# regsimple2addfp.net
KiCad netlist of a schematic drawn in EAGLE
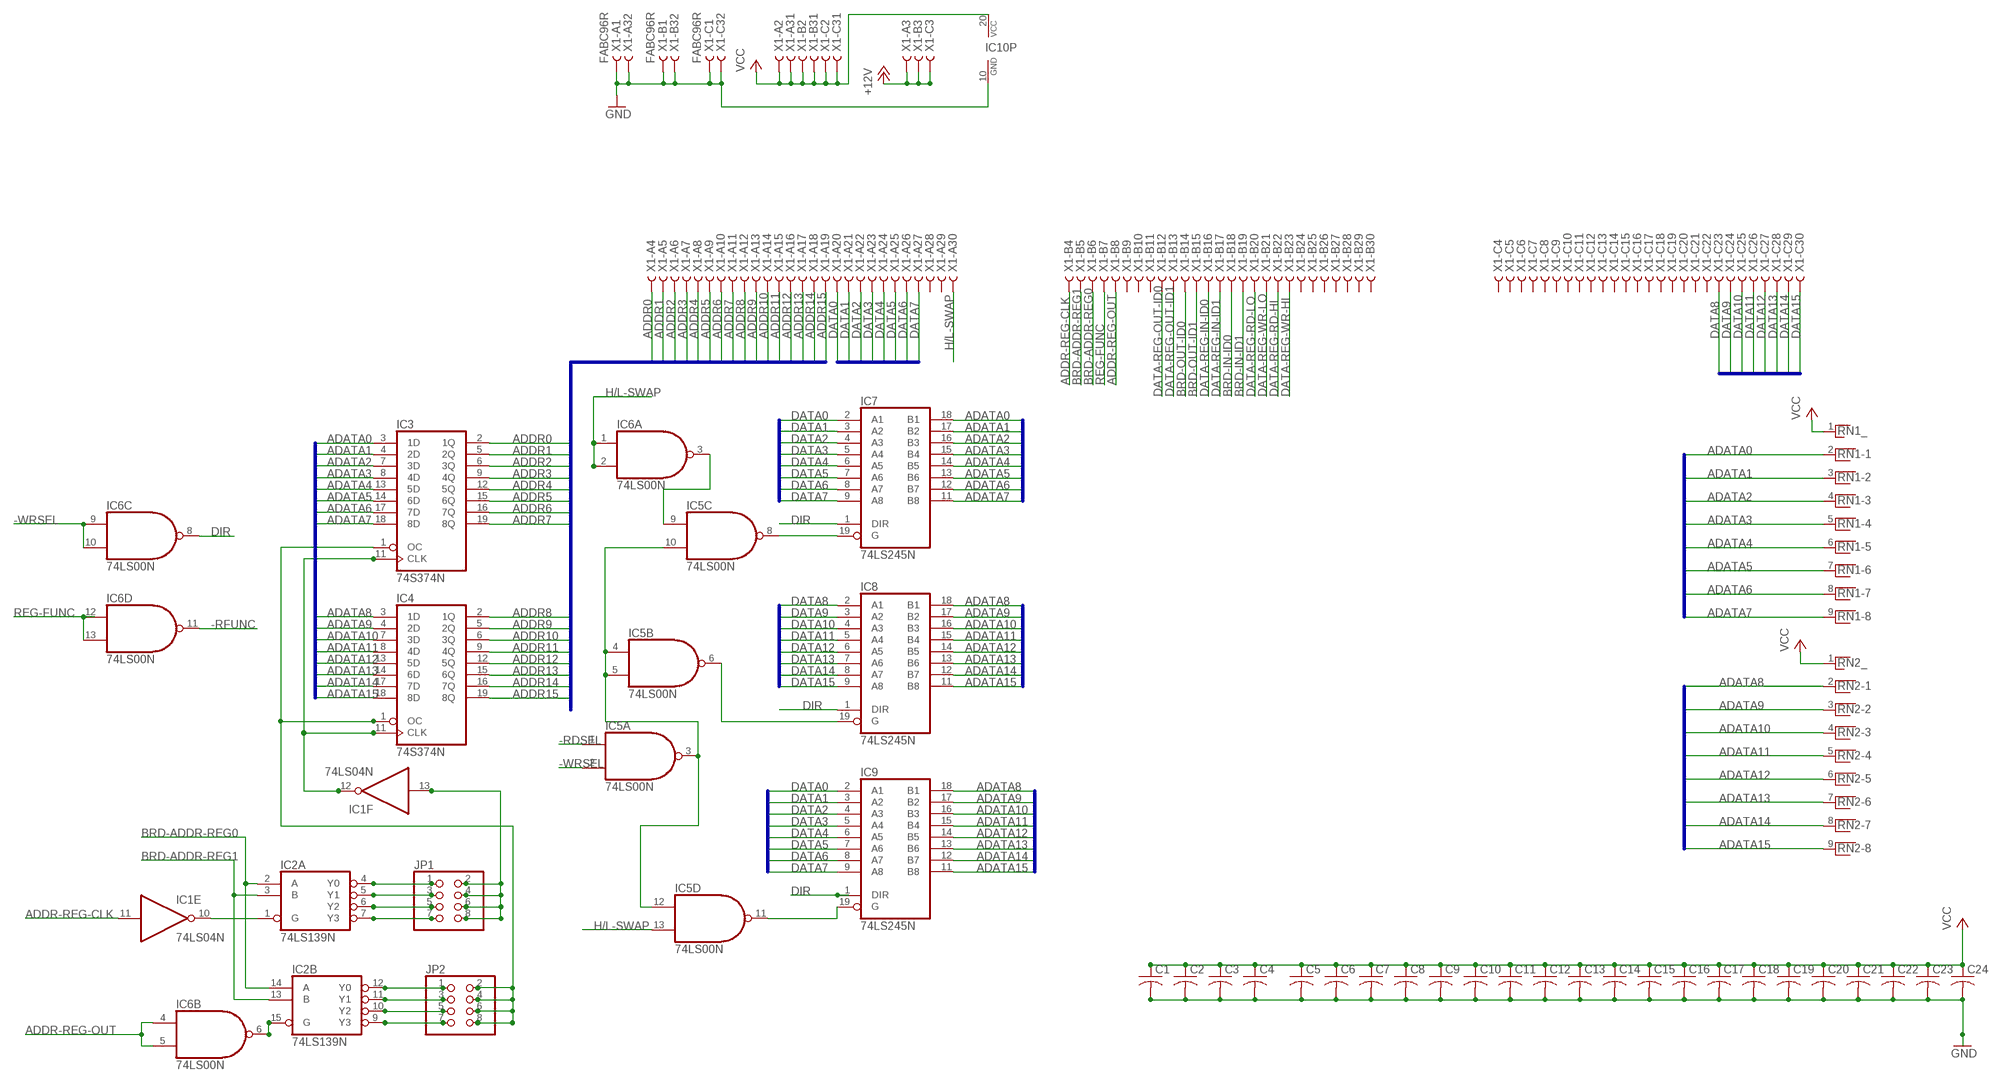
[diagram p0: schematic, sheet 1]
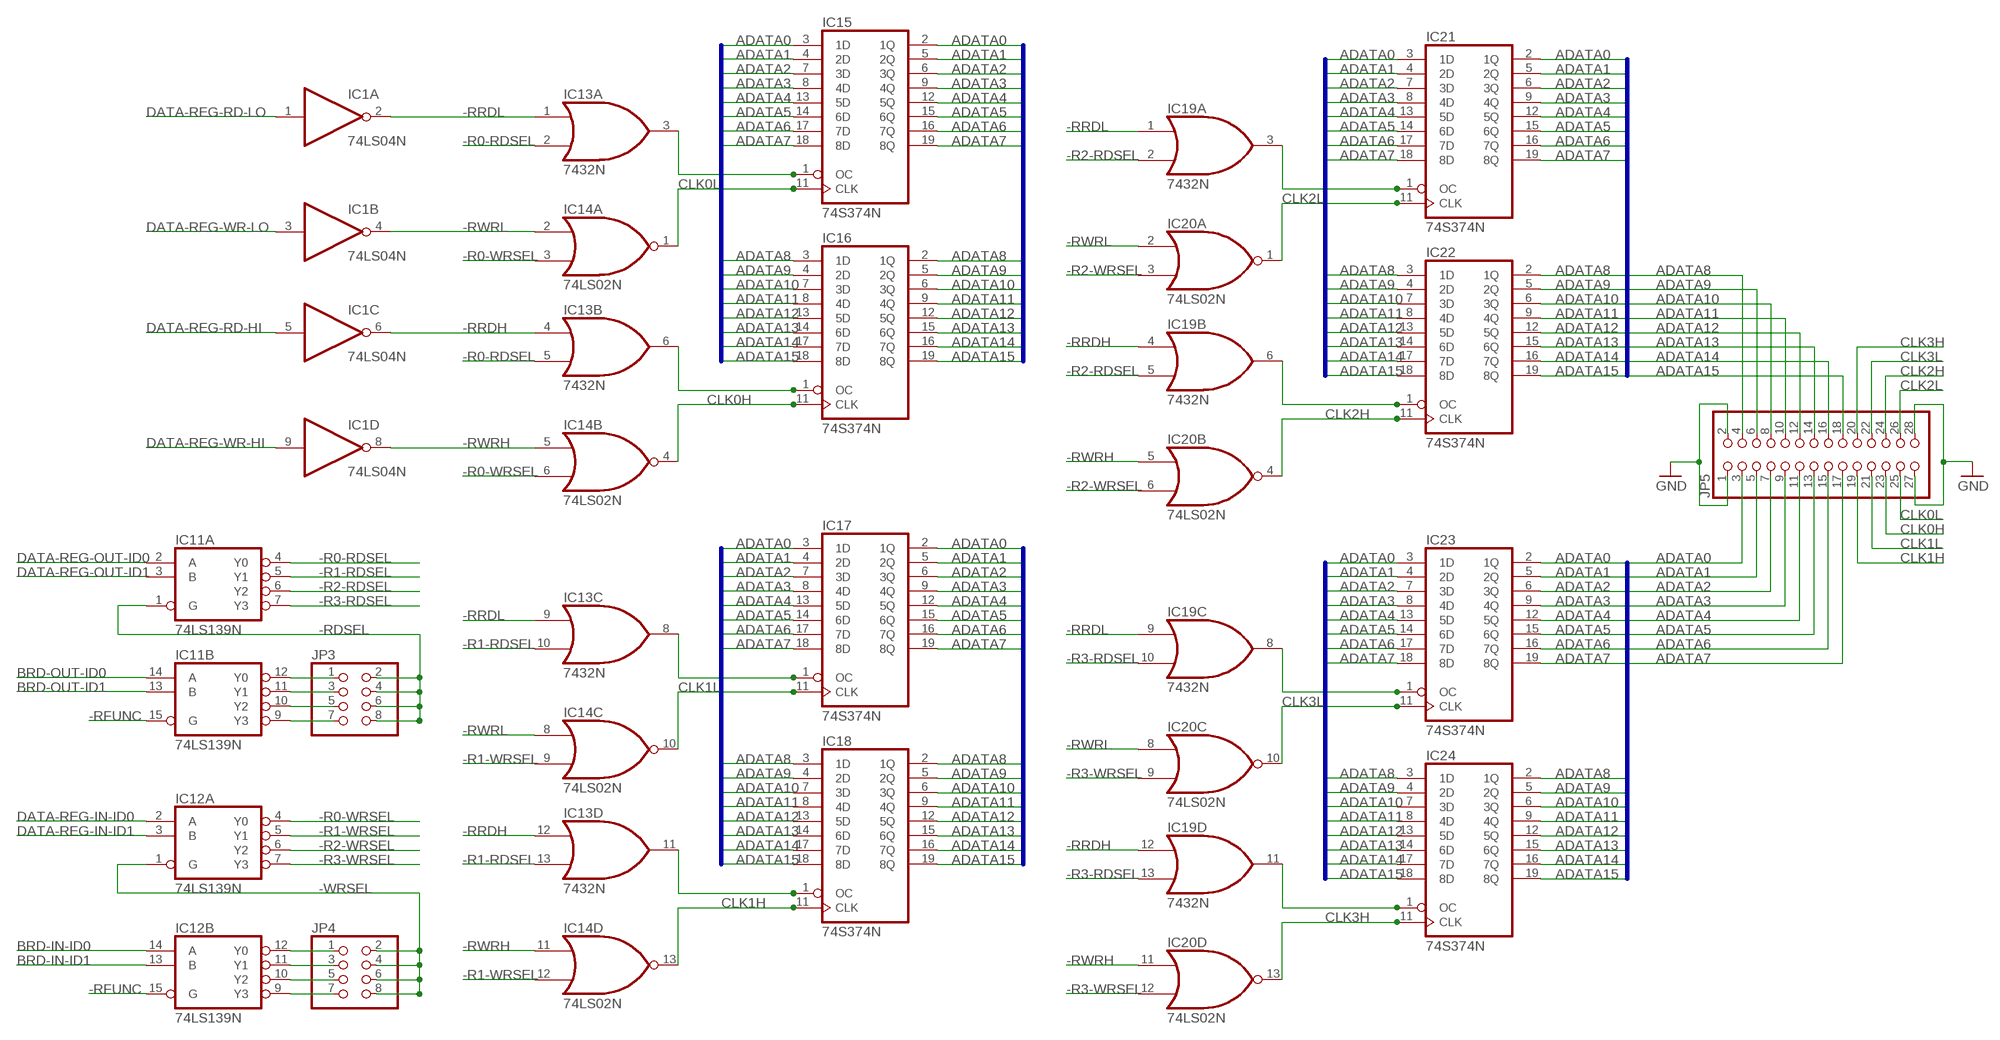
[diagram p1: schematic, sheet 2]

(export (version "E")
  (design (tool "Eeschema 10.0.6"))
  (components
    (comp (ref "IC1")
      (value "74LS04N")
      (footprint "eagle-import:DIL14")
      (libsource (lib "eagle-import") (part "7404NLS"))
    )
    (comp (ref "IC11")
      (value "74LS139N")
      (footprint "eagle-import:DIL16")
      (libsource (lib "eagle-import") (part "74139NLS"))
    )
    (comp (ref "IC12")
      (value "74LS139N")
      (footprint "eagle-import:DIL16")
      (libsource (lib "eagle-import") (part "74139NLS"))
    )
    (comp (ref "IC13")
      (value "7432N")
      (footprint "eagle-import:DIL14")
      (libsource (lib "eagle-import") (part "7432N"))
    )
    (comp (ref "IC14")
      (value "74LS02N")
      (footprint "eagle-import:DIL14")
      (libsource (lib "eagle-import") (part "7402NLS"))
    )
    (comp (ref "IC15")
      (value "74S374N")
      (footprint "eagle-import:DIL20")
      (libsource (lib "eagle-import") (part "74374NS"))
    )
    (comp (ref "IC16")
      (value "74S374N")
      (footprint "eagle-import:DIL20")
      (libsource (lib "eagle-import") (part "74374NS"))
    )
    (comp (ref "IC17")
      (value "74S374N")
      (footprint "eagle-import:DIL20")
      (libsource (lib "eagle-import") (part "74374NS"))
    )
    (comp (ref "IC18")
      (value "74S374N")
      (footprint "eagle-import:DIL20")
      (libsource (lib "eagle-import") (part "74374NS"))
    )
    (comp (ref "IC19")
      (value "7432N")
      (footprint "eagle-import:DIL14")
      (libsource (lib "eagle-import") (part "7432N"))
    )
    (comp (ref "IC20")
      (value "74LS02N")
      (footprint "eagle-import:DIL14")
      (libsource (lib "eagle-import") (part "7402NLS"))
    )
    (comp (ref "IC21")
      (value "74S374N")
      (footprint "eagle-import:DIL20")
      (libsource (lib "eagle-import") (part "74374NS"))
    )
    (comp (ref "IC22")
      (value "74S374N")
      (footprint "eagle-import:DIL20")
      (libsource (lib "eagle-import") (part "74374NS"))
    )
    (comp (ref "IC23")
      (value "74S374N")
      (footprint "eagle-import:DIL20")
      (libsource (lib "eagle-import") (part "74374NS"))
    )
    (comp (ref "IC24")
      (value "74S374N")
      (footprint "eagle-import:DIL20")
      (libsource (lib "eagle-import") (part "74374NS"))
    )
    (comp (ref "JP3")
      (value "PINHD-2X4")
      (footprint "eagle-import:2X04")
      (libsource (lib "eagle-import") (part "PINHD-2X4"))
    )
    (comp (ref "JP4")
      (value "PINHD-2X4")
      (footprint "eagle-import:2X04")
      (libsource (lib "eagle-import") (part "PINHD-2X4"))
    )
    (comp (ref "JP5")
      (value "PINHD-2X14")
      (footprint "eagle-import:2X14")
      (libsource (lib "eagle-import") (part "PINHD-2X14"))
    )
    (comp (ref "C1")
      (value "C-US025-040X050")
      (footprint "eagle-import:C025-040X050")
      (libsource (lib "eagle-import") (part "C-US025-040X050"))
    )
    (comp (ref "C2")
      (value "C-US025-040X050")
      (footprint "eagle-import:C025-040X050")
      (libsource (lib "eagle-import") (part "C-US025-040X050"))
    )
    (comp (ref "C3")
      (value "C-US025-040X050")
      (footprint "eagle-import:C025-040X050")
      (libsource (lib "eagle-import") (part "C-US025-040X050"))
    )
    (comp (ref "C4")
      (value "C-US025-040X050")
      (footprint "eagle-import:C025-040X050")
      (libsource (lib "eagle-import") (part "C-US025-040X050"))
    )
    (comp (ref "C5")
      (value "C-US025-040X050")
      (footprint "eagle-import:C025-040X050")
      (libsource (lib "eagle-import") (part "C-US025-040X050"))
    )
    (comp (ref "C6")
      (value "C-US025-040X050")
      (footprint "eagle-import:C025-040X050")
      (libsource (lib "eagle-import") (part "C-US025-040X050"))
    )
    (comp (ref "C7")
      (value "C-US025-040X050")
      (footprint "eagle-import:C025-040X050")
      (libsource (lib "eagle-import") (part "C-US025-040X050"))
    )
    (comp (ref "C8")
      (value "C-US025-040X050")
      (footprint "eagle-import:C025-040X050")
      (libsource (lib "eagle-import") (part "C-US025-040X050"))
    )
    (comp (ref "C9")
      (value "C-US025-040X050")
      (footprint "eagle-import:C025-040X050")
      (libsource (lib "eagle-import") (part "C-US025-040X050"))
    )
    (comp (ref "C10")
      (value "C-US025-040X050")
      (footprint "eagle-import:C025-040X050")
      (libsource (lib "eagle-import") (part "C-US025-040X050"))
    )
    (comp (ref "C11")
      (value "C-US025-040X050")
      (footprint "eagle-import:C025-040X050")
      (libsource (lib "eagle-import") (part "C-US025-040X050"))
    )
    (comp (ref "C12")
      (value "C-US025-040X050")
      (footprint "eagle-import:C025-040X050")
      (libsource (lib "eagle-import") (part "C-US025-040X050"))
    )
    (comp (ref "C13")
      (value "C-US025-040X050")
      (footprint "eagle-import:C025-040X050")
      (libsource (lib "eagle-import") (part "C-US025-040X050"))
    )
    (comp (ref "C14")
      (value "C-US025-040X050")
      (footprint "eagle-import:C025-040X050")
      (libsource (lib "eagle-import") (part "C-US025-040X050"))
    )
    (comp (ref "C15")
      (value "C-US025-040X050")
      (footprint "eagle-import:C025-040X050")
      (libsource (lib "eagle-import") (part "C-US025-040X050"))
    )
    (comp (ref "C16")
      (value "C-US025-040X050")
      (footprint "eagle-import:C025-040X050")
      (libsource (lib "eagle-import") (part "C-US025-040X050"))
    )
    (comp (ref "C17")
      (value "C-US025-040X050")
      (footprint "eagle-import:C025-040X050")
      (libsource (lib "eagle-import") (part "C-US025-040X050"))
    )
    (comp (ref "C18")
      (value "C-US025-040X050")
      (footprint "eagle-import:C025-040X050")
      (libsource (lib "eagle-import") (part "C-US025-040X050"))
    )
    (comp (ref "C19")
      (value "C-US025-040X050")
      (footprint "eagle-import:C025-040X050")
      (libsource (lib "eagle-import") (part "C-US025-040X050"))
    )
    (comp (ref "C20")
      (value "C-US025-040X050")
      (footprint "eagle-import:C025-040X050")
      (libsource (lib "eagle-import") (part "C-US025-040X050"))
    )
    (comp (ref "C21")
      (value "C-US025-040X050")
      (footprint "eagle-import:C025-040X050")
      (libsource (lib "eagle-import") (part "C-US025-040X050"))
    )
    (comp (ref "C22")
      (value "C-US025-040X050")
      (footprint "eagle-import:C025-040X050")
      (libsource (lib "eagle-import") (part "C-US025-040X050"))
    )
    (comp (ref "C23")
      (value "C-US025-040X050")
      (footprint "eagle-import:C025-040X050")
      (libsource (lib "eagle-import") (part "C-US025-040X050"))
    )
    (comp (ref "C24")
      (value "C-US025-040X050")
      (footprint "eagle-import:C025-040X050")
      (libsource (lib "eagle-import") (part "C-US025-040X050"))
    )
    (comp (ref "IC2")
      (value "74LS139N")
      (footprint "eagle-import:DIL16")
      (libsource (lib "eagle-import") (part "74139NLS"))
    )
    (comp (ref "IC3")
      (value "74S374N")
      (footprint "eagle-import:DIL20")
      (libsource (lib "eagle-import") (part "74374NS"))
    )
    (comp (ref "IC4")
      (value "74S374N")
      (footprint "eagle-import:DIL20")
      (libsource (lib "eagle-import") (part "74374NS"))
    )
    (comp (ref "IC5")
      (value "74LS00N")
      (footprint "eagle-import:DIL14")
      (libsource (lib "eagle-import") (part "7400NLS"))
    )
    (comp (ref "IC6")
      (value "74LS00N")
      (footprint "eagle-import:DIL14")
      (libsource (lib "eagle-import") (part "7400NLS"))
    )
    (comp (ref "IC7")
      (value "74LS245N")
      (footprint "eagle-import:DIL20")
      (libsource (lib "eagle-import") (part "74245NLS"))
    )
    (comp (ref "IC8")
      (value "74LS245N")
      (footprint "eagle-import:DIL20")
      (libsource (lib "eagle-import") (part "74245NLS"))
    )
    (comp (ref "IC9")
      (value "74LS245N")
      (footprint "eagle-import:DIL20")
      (libsource (lib "eagle-import") (part "74245NLS"))
    )
    (comp (ref "IC10")
      (value "74S244N")
      (footprint "eagle-import:DIL20")
      (libsource (lib "eagle-import") (part "74244NS"))
    )
    (comp (ref "JP1")
      (value "PINHD-2X4")
      (footprint "eagle-import:2X04")
      (libsource (lib "eagle-import") (part "PINHD-2X4"))
    )
    (comp (ref "JP2")
      (value "PINHD-2X4")
      (footprint "eagle-import:2X04")
      (libsource (lib "eagle-import") (part "PINHD-2X4"))
    )
    (comp (ref "RN1")
      (value "RNX8")
      (footprint "eagle-import:RN-9")
      (libsource (lib "eagle-import") (part "RNX8"))
    )
    (comp (ref "RN2")
      (value "RNX8")
      (footprint "eagle-import:RN-9")
      (libsource (lib "eagle-import") (part "RNX8"))
    )
    (comp (ref "X1")
      (value "FABC96R")
      (footprint "eagle-import:FABC96R")
      (libsource (lib "eagle-import") (part "FABC96R"))
    )
  )
  (nets
    (net (code "1") (name "+12V") (class "Default")
      (node (ref "X1") (pin "A3") (pinfunction "B_A3") (pintype "passive"))
      (node (ref "X1") (pin "B3") (pinfunction "B_B3") (pintype "passive"))
      (node (ref "X1") (pin "C3") (pinfunction "B_C3") (pintype "passive"))
    )
    (net (code "2") (name "-R0-RDSEL") (class "Default")
      (node (ref "IC11") (pin "4") (pinfunction "Y0_4") (pintype "output"))
      (node (ref "IC13") (pin "2") (pinfunction "I1_2") (pintype "input"))
      (node (ref "IC13") (pin "5") (pinfunction "I1_5") (pintype "input"))
    )
    (net (code "3") (name "-R0-WRSEL") (class "Default")
      (node (ref "IC12") (pin "4") (pinfunction "Y0_4") (pintype "output"))
      (node (ref "IC14") (pin "3") (pinfunction "I1_3") (pintype "input"))
      (node (ref "IC14") (pin "6") (pinfunction "I1_6") (pintype "input"))
    )
    (net (code "4") (name "-R1-RDSEL") (class "Default")
      (node (ref "IC11") (pin "5") (pinfunction "Y1_5") (pintype "output"))
      (node (ref "IC13") (pin "10") (pinfunction "I1_10") (pintype "input"))
      (node (ref "IC13") (pin "13") (pinfunction "I1_13") (pintype "input"))
    )
    (net (code "5") (name "-R1-WRSEL") (class "Default")
      (node (ref "IC12") (pin "5") (pinfunction "Y1_5") (pintype "output"))
      (node (ref "IC14") (pin "12") (pinfunction "I1_12") (pintype "input"))
      (node (ref "IC14") (pin "9") (pinfunction "I1_9") (pintype "input"))
    )
    (net (code "6") (name "-R2-RDSEL") (class "Default")
      (node (ref "IC11") (pin "6") (pinfunction "Y2_6") (pintype "output"))
      (node (ref "IC19") (pin "2") (pinfunction "I1_2") (pintype "input"))
      (node (ref "IC19") (pin "5") (pinfunction "I1_5") (pintype "input"))
    )
    (net (code "7") (name "-R2-WRSEL") (class "Default")
      (node (ref "IC12") (pin "6") (pinfunction "Y2_6") (pintype "output"))
      (node (ref "IC20") (pin "3") (pinfunction "I1_3") (pintype "input"))
      (node (ref "IC20") (pin "6") (pinfunction "I1_6") (pintype "input"))
    )
    (net (code "8") (name "-R3-RDSEL") (class "Default")
      (node (ref "IC11") (pin "7") (pinfunction "Y3_7") (pintype "output"))
      (node (ref "IC19") (pin "10") (pinfunction "I1_10") (pintype "input"))
      (node (ref "IC19") (pin "13") (pinfunction "I1_13") (pintype "input"))
    )
    (net (code "9") (name "-R3-WRSEL") (class "Default")
      (node (ref "IC12") (pin "7") (pinfunction "Y3_7") (pintype "output"))
      (node (ref "IC20") (pin "12") (pinfunction "I1_12") (pintype "input"))
      (node (ref "IC20") (pin "9") (pinfunction "I1_9") (pintype "input"))
    )
    (net (code "10") (name "-RDSEL") (class "Default")
      (node (ref "IC11") (pin "1") (pinfunction "G_1") (pintype "input"))
      (node (ref "IC5") (pin "1") (pinfunction "I0_1") (pintype "input"))
      (node (ref "JP3") (pin "2") (pinfunction "2_2") (pintype "passive"))
      (node (ref "JP3") (pin "4") (pinfunction "4_4") (pintype "passive"))
      (node (ref "JP3") (pin "6") (pinfunction "6_6") (pintype "passive"))
      (node (ref "JP3") (pin "8") (pinfunction "8_8") (pintype "passive"))
    )
    (net (code "11") (name "-RFUNC") (class "Default")
      (node (ref "IC11") (pin "15") (pinfunction "G_15") (pintype "input"))
      (node (ref "IC12") (pin "15") (pinfunction "G_15") (pintype "input"))
      (node (ref "IC6") (pin "11") (pinfunction "O_11") (pintype "output"))
    )
    (net (code "12") (name "-RRDH") (class "Default")
      (node (ref "IC1") (pin "6") (pinfunction "O_6") (pintype "output"))
      (node (ref "IC13") (pin "12") (pinfunction "I0_12") (pintype "input"))
      (node (ref "IC13") (pin "4") (pinfunction "I0_4") (pintype "input"))
      (node (ref "IC19") (pin "12") (pinfunction "I0_12") (pintype "input"))
      (node (ref "IC19") (pin "4") (pinfunction "I0_4") (pintype "input"))
    )
    (net (code "13") (name "-RRDL") (class "Default")
      (node (ref "IC1") (pin "2") (pinfunction "O_2") (pintype "output"))
      (node (ref "IC13") (pin "1") (pinfunction "I0_1") (pintype "input"))
      (node (ref "IC13") (pin "9") (pinfunction "I0_9") (pintype "input"))
      (node (ref "IC19") (pin "1") (pinfunction "I0_1") (pintype "input"))
      (node (ref "IC19") (pin "9") (pinfunction "I0_9") (pintype "input"))
    )
    (net (code "14") (name "-RWRH") (class "Default")
      (node (ref "IC1") (pin "8") (pinfunction "O_8") (pintype "output"))
      (node (ref "IC14") (pin "11") (pinfunction "I0_11") (pintype "input"))
      (node (ref "IC14") (pin "5") (pinfunction "I0_5") (pintype "input"))
      (node (ref "IC20") (pin "11") (pinfunction "I0_11") (pintype "input"))
      (node (ref "IC20") (pin "5") (pinfunction "I0_5") (pintype "input"))
    )
    (net (code "15") (name "-RWRL") (class "Default")
      (node (ref "IC1") (pin "4") (pinfunction "O_4") (pintype "output"))
      (node (ref "IC14") (pin "2") (pinfunction "I0_2") (pintype "input"))
      (node (ref "IC14") (pin "8") (pinfunction "I0_8") (pintype "input"))
      (node (ref "IC20") (pin "2") (pinfunction "I0_2") (pintype "input"))
      (node (ref "IC20") (pin "8") (pinfunction "I0_8") (pintype "input"))
    )
    (net (code "16") (name "-WRSEL") (class "Default")
      (node (ref "IC12") (pin "1") (pinfunction "G_1") (pintype "input"))
      (node (ref "IC5") (pin "2") (pinfunction "I1_2") (pintype "input"))
      (node (ref "IC6") (pin "10") (pinfunction "I1_10") (pintype "input"))
      (node (ref "IC6") (pin "9") (pinfunction "I0_9") (pintype "input"))
      (node (ref "JP4") (pin "2") (pinfunction "2_2") (pintype "passive"))
      (node (ref "JP4") (pin "4") (pinfunction "4_4") (pintype "passive"))
      (node (ref "JP4") (pin "6") (pinfunction "6_6") (pintype "passive"))
      (node (ref "JP4") (pin "8") (pinfunction "8_8") (pintype "passive"))
    )
    (net (code "17") (name "ADATA0") (class "Default")
      (node (ref "IC15") (pin "2") (pinfunction "1Q_2") (pintype "tri_state"))
      (node (ref "IC15") (pin "3") (pinfunction "1D_3") (pintype "input"))
      (node (ref "IC17") (pin "2") (pinfunction "1Q_2") (pintype "tri_state"))
      (node (ref "IC17") (pin "3") (pinfunction "1D_3") (pintype "input"))
      (node (ref "IC21") (pin "2") (pinfunction "1Q_2") (pintype "tri_state"))
      (node (ref "IC21") (pin "3") (pinfunction "1D_3") (pintype "input"))
      (node (ref "IC23") (pin "2") (pinfunction "1Q_2") (pintype "tri_state"))
      (node (ref "IC23") (pin "3") (pinfunction "1D_3") (pintype "input"))
      (node (ref "IC3") (pin "3") (pinfunction "1D_3") (pintype "input"))
      (node (ref "IC7") (pin "18") (pinfunction "B1_18") (pintype "bidirectional"))
      (node (ref "JP5") (pin "3") (pinfunction "3_3") (pintype "passive"))
      (node (ref "RN1") (pin "2") (pinfunction "1_2") (pintype "passive"))
    )
    (net (code "18") (name "ADATA1") (class "Default")
      (node (ref "IC15") (pin "4") (pinfunction "2D_4") (pintype "input"))
      (node (ref "IC15") (pin "5") (pinfunction "2Q_5") (pintype "tri_state"))
      (node (ref "IC17") (pin "4") (pinfunction "2D_4") (pintype "input"))
      (node (ref "IC17") (pin "5") (pinfunction "2Q_5") (pintype "tri_state"))
      (node (ref "IC21") (pin "4") (pinfunction "2D_4") (pintype "input"))
      (node (ref "IC21") (pin "5") (pinfunction "2Q_5") (pintype "tri_state"))
      (node (ref "IC23") (pin "4") (pinfunction "2D_4") (pintype "input"))
      (node (ref "IC23") (pin "5") (pinfunction "2Q_5") (pintype "tri_state"))
      (node (ref "IC3") (pin "4") (pinfunction "2D_4") (pintype "input"))
      (node (ref "IC7") (pin "17") (pinfunction "B2_17") (pintype "bidirectional"))
      (node (ref "JP5") (pin "5") (pinfunction "5_5") (pintype "passive"))
      (node (ref "RN1") (pin "3") (pinfunction "1_3") (pintype "passive"))
    )
    (net (code "19") (name "ADATA2") (class "Default")
      (node (ref "IC15") (pin "6") (pinfunction "3Q_6") (pintype "tri_state"))
      (node (ref "IC15") (pin "7") (pinfunction "3D_7") (pintype "input"))
      (node (ref "IC17") (pin "6") (pinfunction "3Q_6") (pintype "tri_state"))
      (node (ref "IC17") (pin "7") (pinfunction "3D_7") (pintype "input"))
      (node (ref "IC21") (pin "6") (pinfunction "3Q_6") (pintype "tri_state"))
      (node (ref "IC21") (pin "7") (pinfunction "3D_7") (pintype "input"))
      (node (ref "IC23") (pin "6") (pinfunction "3Q_6") (pintype "tri_state"))
      (node (ref "IC23") (pin "7") (pinfunction "3D_7") (pintype "input"))
      (node (ref "IC3") (pin "7") (pinfunction "3D_7") (pintype "input"))
      (node (ref "IC7") (pin "16") (pinfunction "B3_16") (pintype "bidirectional"))
      (node (ref "JP5") (pin "7") (pinfunction "7_7") (pintype "passive"))
      (node (ref "RN1") (pin "4") (pinfunction "1_4") (pintype "passive"))
    )
    (net (code "20") (name "ADATA3") (class "Default")
      (node (ref "IC15") (pin "8") (pinfunction "4D_8") (pintype "input"))
      (node (ref "IC15") (pin "9") (pinfunction "4Q_9") (pintype "tri_state"))
      (node (ref "IC17") (pin "8") (pinfunction "4D_8") (pintype "input"))
      (node (ref "IC17") (pin "9") (pinfunction "4Q_9") (pintype "tri_state"))
      (node (ref "IC21") (pin "8") (pinfunction "4D_8") (pintype "input"))
      (node (ref "IC21") (pin "9") (pinfunction "4Q_9") (pintype "tri_state"))
      (node (ref "IC23") (pin "8") (pinfunction "4D_8") (pintype "input"))
      (node (ref "IC23") (pin "9") (pinfunction "4Q_9") (pintype "tri_state"))
      (node (ref "IC3") (pin "8") (pinfunction "4D_8") (pintype "input"))
      (node (ref "IC7") (pin "15") (pinfunction "B4_15") (pintype "bidirectional"))
      (node (ref "JP5") (pin "9") (pinfunction "9_9") (pintype "passive"))
      (node (ref "RN1") (pin "5") (pinfunction "1_5") (pintype "passive"))
    )
    (net (code "21") (name "ADATA4") (class "Default")
      (node (ref "IC15") (pin "12") (pinfunction "5Q_12") (pintype "tri_state"))
      (node (ref "IC15") (pin "13") (pinfunction "5D_13") (pintype "input"))
      (node (ref "IC17") (pin "12") (pinfunction "5Q_12") (pintype "tri_state"))
      (node (ref "IC17") (pin "13") (pinfunction "5D_13") (pintype "input"))
      (node (ref "IC21") (pin "12") (pinfunction "5Q_12") (pintype "tri_state"))
      (node (ref "IC21") (pin "13") (pinfunction "5D_13") (pintype "input"))
      (node (ref "IC23") (pin "12") (pinfunction "5Q_12") (pintype "tri_state"))
      (node (ref "IC23") (pin "13") (pinfunction "5D_13") (pintype "input"))
      (node (ref "IC3") (pin "13") (pinfunction "5D_13") (pintype "input"))
      (node (ref "IC7") (pin "14") (pinfunction "B5_14") (pintype "bidirectional"))
      (node (ref "JP5") (pin "11") (pinfunction "11_11") (pintype "passive"))
      (node (ref "RN1") (pin "6") (pinfunction "1_6") (pintype "passive"))
    )
    (net (code "22") (name "ADATA5") (class "Default")
      (node (ref "IC15") (pin "14") (pinfunction "6D_14") (pintype "input"))
      (node (ref "IC15") (pin "15") (pinfunction "6Q_15") (pintype "tri_state"))
      (node (ref "IC17") (pin "14") (pinfunction "6D_14") (pintype "input"))
      (node (ref "IC17") (pin "15") (pinfunction "6Q_15") (pintype "tri_state"))
      (node (ref "IC21") (pin "14") (pinfunction "6D_14") (pintype "input"))
      (node (ref "IC21") (pin "15") (pinfunction "6Q_15") (pintype "tri_state"))
      (node (ref "IC23") (pin "14") (pinfunction "6D_14") (pintype "input"))
      (node (ref "IC23") (pin "15") (pinfunction "6Q_15") (pintype "tri_state"))
      (node (ref "IC3") (pin "14") (pinfunction "6D_14") (pintype "input"))
      (node (ref "IC7") (pin "13") (pinfunction "B6_13") (pintype "bidirectional"))
      (node (ref "JP5") (pin "13") (pinfunction "13_13") (pintype "passive"))
      (node (ref "RN1") (pin "7") (pinfunction "1_7") (pintype "passive"))
    )
    (net (code "23") (name "ADATA6") (class "Default")
      (node (ref "IC15") (pin "16") (pinfunction "7Q_16") (pintype "tri_state"))
      (node (ref "IC15") (pin "17") (pinfunction "7D_17") (pintype "input"))
      (node (ref "IC17") (pin "16") (pinfunction "7Q_16") (pintype "tri_state"))
      (node (ref "IC17") (pin "17") (pinfunction "7D_17") (pintype "input"))
      (node (ref "IC21") (pin "16") (pinfunction "7Q_16") (pintype "tri_state"))
      (node (ref "IC21") (pin "17") (pinfunction "7D_17") (pintype "input"))
      (node (ref "IC23") (pin "16") (pinfunction "7Q_16") (pintype "tri_state"))
      (node (ref "IC23") (pin "17") (pinfunction "7D_17") (pintype "input"))
      (node (ref "IC3") (pin "17") (pinfunction "7D_17") (pintype "input"))
      (node (ref "IC7") (pin "12") (pinfunction "B7_12") (pintype "bidirectional"))
      (node (ref "JP5") (pin "15") (pinfunction "15_15") (pintype "passive"))
      (node (ref "RN1") (pin "8") (pinfunction "1_8") (pintype "passive"))
    )
    (net (code "24") (name "ADATA7") (class "Default")
      (node (ref "IC15") (pin "18") (pinfunction "8D_18") (pintype "input"))
      (node (ref "IC15") (pin "19") (pinfunction "8Q_19") (pintype "tri_state"))
      (node (ref "IC17") (pin "18") (pinfunction "8D_18") (pintype "input"))
      (node (ref "IC17") (pin "19") (pinfunction "8Q_19") (pintype "tri_state"))
      (node (ref "IC21") (pin "18") (pinfunction "8D_18") (pintype "input"))
      (node (ref "IC21") (pin "19") (pinfunction "8Q_19") (pintype "tri_state"))
      (node (ref "IC23") (pin "18") (pinfunction "8D_18") (pintype "input"))
      (node (ref "IC23") (pin "19") (pinfunction "8Q_19") (pintype "tri_state"))
      (node (ref "IC3") (pin "18") (pinfunction "8D_18") (pintype "input"))
      (node (ref "IC7") (pin "11") (pinfunction "B8_11") (pintype "bidirectional"))
      (node (ref "JP5") (pin "17") (pinfunction "17_17") (pintype "passive"))
      (node (ref "RN1") (pin "9") (pinfunction "1_9") (pintype "passive"))
    )
    (net (code "25") (name "ADATA8") (class "Default")
      (node (ref "IC16") (pin "2") (pinfunction "1Q_2") (pintype "tri_state"))
      (node (ref "IC16") (pin "3") (pinfunction "1D_3") (pintype "input"))
      (node (ref "IC18") (pin "2") (pinfunction "1Q_2") (pintype "tri_state"))
      (node (ref "IC18") (pin "3") (pinfunction "1D_3") (pintype "input"))
      (node (ref "IC22") (pin "2") (pinfunction "1Q_2") (pintype "tri_state"))
      (node (ref "IC22") (pin "3") (pinfunction "1D_3") (pintype "input"))
      (node (ref "IC24") (pin "2") (pinfunction "1Q_2") (pintype "tri_state"))
      (node (ref "IC24") (pin "3") (pinfunction "1D_3") (pintype "input"))
      (node (ref "IC4") (pin "3") (pinfunction "1D_3") (pintype "input"))
      (node (ref "IC8") (pin "18") (pinfunction "B1_18") (pintype "bidirectional"))
      (node (ref "IC9") (pin "18") (pinfunction "B1_18") (pintype "bidirectional"))
      (node (ref "JP5") (pin "4") (pinfunction "4_4") (pintype "passive"))
      (node (ref "RN2") (pin "2") (pinfunction "1_2") (pintype "passive"))
    )
    (net (code "26") (name "ADATA9") (class "Default")
      (node (ref "IC16") (pin "4") (pinfunction "2D_4") (pintype "input"))
      (node (ref "IC16") (pin "5") (pinfunction "2Q_5") (pintype "tri_state"))
      (node (ref "IC18") (pin "4") (pinfunction "2D_4") (pintype "input"))
      (node (ref "IC18") (pin "5") (pinfunction "2Q_5") (pintype "tri_state"))
      (node (ref "IC22") (pin "4") (pinfunction "2D_4") (pintype "input"))
      (node (ref "IC22") (pin "5") (pinfunction "2Q_5") (pintype "tri_state"))
      (node (ref "IC24") (pin "4") (pinfunction "2D_4") (pintype "input"))
      (node (ref "IC24") (pin "5") (pinfunction "2Q_5") (pintype "tri_state"))
      (node (ref "IC4") (pin "4") (pinfunction "2D_4") (pintype "input"))
      (node (ref "IC8") (pin "17") (pinfunction "B2_17") (pintype "bidirectional"))
      (node (ref "IC9") (pin "17") (pinfunction "B2_17") (pintype "bidirectional"))
      (node (ref "JP5") (pin "6") (pinfunction "6_6") (pintype "passive"))
      (node (ref "RN2") (pin "3") (pinfunction "1_3") (pintype "passive"))
    )
    (net (code "27") (name "ADATA10") (class "Default")
      (node (ref "IC16") (pin "6") (pinfunction "3Q_6") (pintype "tri_state"))
      (node (ref "IC16") (pin "7") (pinfunction "3D_7") (pintype "input"))
      (node (ref "IC18") (pin "6") (pinfunction "3Q_6") (pintype "tri_state"))
      (node (ref "IC18") (pin "7") (pinfunction "3D_7") (pintype "input"))
      (node (ref "IC22") (pin "6") (pinfunction "3Q_6") (pintype "tri_state"))
      (node (ref "IC22") (pin "7") (pinfunction "3D_7") (pintype "input"))
      (node (ref "IC24") (pin "6") (pinfunction "3Q_6") (pintype "tri_state"))
      (node (ref "IC24") (pin "7") (pinfunction "3D_7") (pintype "input"))
      (node (ref "IC4") (pin "7") (pinfunction "3D_7") (pintype "input"))
      (node (ref "IC8") (pin "16") (pinfunction "B3_16") (pintype "bidirectional"))
      (node (ref "IC9") (pin "16") (pinfunction "B3_16") (pintype "bidirectional"))
      (node (ref "JP5") (pin "8") (pinfunction "8_8") (pintype "passive"))
      (node (ref "RN2") (pin "4") (pinfunction "1_4") (pintype "passive"))
    )
    (net (code "28") (name "ADATA11") (class "Default")
      (node (ref "IC16") (pin "8") (pinfunction "4D_8") (pintype "input"))
      (node (ref "IC16") (pin "9") (pinfunction "4Q_9") (pintype "tri_state"))
      (node (ref "IC18") (pin "8") (pinfunction "4D_8") (pintype "input"))
      (node (ref "IC18") (pin "9") (pinfunction "4Q_9") (pintype "tri_state"))
      (node (ref "IC22") (pin "8") (pinfunction "4D_8") (pintype "input"))
      (node (ref "IC22") (pin "9") (pinfunction "4Q_9") (pintype "tri_state"))
      (node (ref "IC24") (pin "8") (pinfunction "4D_8") (pintype "input"))
      (node (ref "IC24") (pin "9") (pinfunction "4Q_9") (pintype "tri_state"))
      (node (ref "IC4") (pin "8") (pinfunction "4D_8") (pintype "input"))
      (node (ref "IC8") (pin "15") (pinfunction "B4_15") (pintype "bidirectional"))
      (node (ref "IC9") (pin "15") (pinfunction "B4_15") (pintype "bidirectional"))
      (node (ref "JP5") (pin "10") (pinfunction "10_10") (pintype "passive"))
      (node (ref "RN2") (pin "5") (pinfunction "1_5") (pintype "passive"))
    )
    (net (code "29") (name "ADATA12") (class "Default")
      (node (ref "IC16") (pin "12") (pinfunction "5Q_12") (pintype "tri_state"))
      (node (ref "IC16") (pin "13") (pinfunction "5D_13") (pintype "input"))
      (node (ref "IC18") (pin "12") (pinfunction "5Q_12") (pintype "tri_state"))
      (node (ref "IC18") (pin "13") (pinfunction "5D_13") (pintype "input"))
      (node (ref "IC22") (pin "12") (pinfunction "5Q_12") (pintype "tri_state"))
      (node (ref "IC22") (pin "13") (pinfunction "5D_13") (pintype "input"))
      (node (ref "IC24") (pin "12") (pinfunction "5Q_12") (pintype "tri_state"))
      (node (ref "IC24") (pin "13") (pinfunction "5D_13") (pintype "input"))
      (node (ref "IC4") (pin "13") (pinfunction "5D_13") (pintype "input"))
      (node (ref "IC8") (pin "14") (pinfunction "B5_14") (pintype "bidirectional"))
      (node (ref "IC9") (pin "14") (pinfunction "B5_14") (pintype "bidirectional"))
      (node (ref "JP5") (pin "12") (pinfunction "12_12") (pintype "passive"))
      (node (ref "RN2") (pin "6") (pinfunction "1_6") (pintype "passive"))
    )
    (net (code "30") (name "ADATA13") (class "Default")
      (node (ref "IC16") (pin "14") (pinfunction "6D_14") (pintype "input"))
      (node (ref "IC16") (pin "15") (pinfunction "6Q_15") (pintype "tri_state"))
      (node (ref "IC18") (pin "14") (pinfunction "6D_14") (pintype "input"))
      (node (ref "IC18") (pin "15") (pinfunction "6Q_15") (pintype "tri_state"))
      (node (ref "IC22") (pin "14") (pinfunction "6D_14") (pintype "input"))
      (node (ref "IC22") (pin "15") (pinfunction "6Q_15") (pintype "tri_state"))
      (node (ref "IC24") (pin "14") (pinfunction "6D_14") (pintype "input"))
      (node (ref "IC24") (pin "15") (pinfunction "6Q_15") (pintype "tri_state"))
      (node (ref "IC4") (pin "14") (pinfunction "6D_14") (pintype "input"))
      (node (ref "IC8") (pin "13") (pinfunction "B6_13") (pintype "bidirectional"))
      (node (ref "IC9") (pin "13") (pinfunction "B6_13") (pintype "bidirectional"))
      (node (ref "JP5") (pin "14") (pinfunction "14_14") (pintype "passive"))
      (node (ref "RN2") (pin "7") (pinfunction "1_7") (pintype "passive"))
    )
    (net (code "31") (name "ADATA14") (class "Default")
      (node (ref "IC16") (pin "16") (pinfunction "7Q_16") (pintype "tri_state"))
      (node (ref "IC16") (pin "17") (pinfunction "7D_17") (pintype "input"))
      (node (ref "IC18") (pin "16") (pinfunction "7Q_16") (pintype "tri_state"))
      (node (ref "IC18") (pin "17") (pinfunction "7D_17") (pintype "input"))
      (node (ref "IC22") (pin "16") (pinfunction "7Q_16") (pintype "tri_state"))
      (node (ref "IC22") (pin "17") (pinfunction "7D_17") (pintype "input"))
      (node (ref "IC24") (pin "16") (pinfunction "7Q_16") (pintype "tri_state"))
      (node (ref "IC24") (pin "17") (pinfunction "7D_17") (pintype "input"))
      (node (ref "IC4") (pin "17") (pinfunction "7D_17") (pintype "input"))
      (node (ref "IC8") (pin "12") (pinfunction "B7_12") (pintype "bidirectional"))
      (node (ref "IC9") (pin "12") (pinfunction "B7_12") (pintype "bidirectional"))
      (node (ref "JP5") (pin "16") (pinfunction "16_16") (pintype "passive"))
      (node (ref "RN2") (pin "8") (pinfunction "1_8") (pintype "passive"))
    )
    (net (code "32") (name "ADATA15") (class "Default")
      (node (ref "IC16") (pin "18") (pinfunction "8D_18") (pintype "input"))
      (node (ref "IC16") (pin "19") (pinfunction "8Q_19") (pintype "tri_state"))
      (node (ref "IC18") (pin "18") (pinfunction "8D_18") (pintype "input"))
      (node (ref "IC18") (pin "19") (pinfunction "8Q_19") (pintype "tri_state"))
      (node (ref "IC22") (pin "18") (pinfunction "8D_18") (pintype "input"))
      (node (ref "IC22") (pin "19") (pinfunction "8Q_19") (pintype "tri_state"))
      (node (ref "IC24") (pin "18") (pinfunction "8D_18") (pintype "input"))
      (node (ref "IC24") (pin "19") (pinfunction "8Q_19") (pintype "tri_state"))
      (node (ref "IC4") (pin "18") (pinfunction "8D_18") (pintype "input"))
      (node (ref "IC8") (pin "11") (pinfunction "B8_11") (pintype "bidirectional"))
      (node (ref "IC9") (pin "11") (pinfunction "B8_11") (pintype "bidirectional"))
      (node (ref "JP5") (pin "18") (pinfunction "18_18") (pintype "passive"))
      (node (ref "RN2") (pin "9") (pinfunction "1_9") (pintype "passive"))
    )
    (net (code "33") (name "ADDR-REG-CLK") (class "Default")
      (node (ref "IC1") (pin "11") (pinfunction "I_11") (pintype "input"))
      (node (ref "X1") (pin "B4") (pinfunction "B_B4") (pintype "passive"))
    )
    (net (code "34") (name "ADDR-REG-OUT") (class "Default")
      (node (ref "IC6") (pin "4") (pinfunction "I0_4") (pintype "input"))
      (node (ref "IC6") (pin "5") (pinfunction "I1_5") (pintype "input"))
      (node (ref "X1") (pin "B8") (pinfunction "B_B8") (pintype "passive"))
    )
    (net (code "35") (name "ADDR0") (class "Default")
      (node (ref "IC3") (pin "2") (pinfunction "1Q_2") (pintype "tri_state"))
      (node (ref "X1") (pin "A4") (pinfunction "B_A4") (pintype "passive"))
    )
    (net (code "36") (name "ADDR1") (class "Default")
      (node (ref "IC3") (pin "5") (pinfunction "2Q_5") (pintype "tri_state"))
      (node (ref "X1") (pin "A5") (pinfunction "B_A5") (pintype "passive"))
    )
    (net (code "37") (name "ADDR2") (class "Default")
      (node (ref "IC3") (pin "6") (pinfunction "3Q_6") (pintype "tri_state"))
      (node (ref "X1") (pin "A6") (pinfunction "B_A6") (pintype "passive"))
    )
    (net (code "38") (name "ADDR3") (class "Default")
      (node (ref "IC3") (pin "9") (pinfunction "4Q_9") (pintype "tri_state"))
      (node (ref "X1") (pin "A7") (pinfunction "B_A7") (pintype "passive"))
    )
    (net (code "39") (name "ADDR4") (class "Default")
      (node (ref "IC3") (pin "12") (pinfunction "5Q_12") (pintype "tri_state"))
      (node (ref "X1") (pin "A8") (pinfunction "B_A8") (pintype "passive"))
    )
    (net (code "40") (name "ADDR5") (class "Default")
      (node (ref "IC3") (pin "15") (pinfunction "6Q_15") (pintype "tri_state"))
      (node (ref "X1") (pin "A9") (pinfunction "B_A9") (pintype "passive"))
    )
    (net (code "41") (name "ADDR6") (class "Default")
      (node (ref "IC3") (pin "16") (pinfunction "7Q_16") (pintype "tri_state"))
      (node (ref "X1") (pin "A10") (pinfunction "B_A10") (pintype "passive"))
    )
    (net (code "42") (name "ADDR7") (class "Default")
      (node (ref "IC3") (pin "19") (pinfunction "8Q_19") (pintype "tri_state"))
      (node (ref "X1") (pin "A11") (pinfunction "B_A11") (pintype "passive"))
    )
    (net (code "43") (name "ADDR8") (class "Default")
      (node (ref "IC4") (pin "2") (pinfunction "1Q_2") (pintype "tri_state"))
      (node (ref "X1") (pin "A12") (pinfunction "B_A12") (pintype "passive"))
    )
    (net (code "44") (name "ADDR9") (class "Default")
      (node (ref "IC4") (pin "5") (pinfunction "2Q_5") (pintype "tri_state"))
      (node (ref "X1") (pin "A13") (pinfunction "B_A13") (pintype "passive"))
    )
    (net (code "45") (name "ADDR10") (class "Default")
      (node (ref "IC4") (pin "6") (pinfunction "3Q_6") (pintype "tri_state"))
      (node (ref "X1") (pin "A14") (pinfunction "B_A14") (pintype "passive"))
    )
    (net (code "46") (name "ADDR11") (class "Default")
      (node (ref "IC4") (pin "9") (pinfunction "4Q_9") (pintype "tri_state"))
      (node (ref "X1") (pin "A15") (pinfunction "B_A15") (pintype "passive"))
    )
    (net (code "47") (name "ADDR12") (class "Default")
      (node (ref "IC4") (pin "12") (pinfunction "5Q_12") (pintype "tri_state"))
      (node (ref "X1") (pin "A16") (pinfunction "B_A16") (pintype "passive"))
    )
    (net (code "48") (name "ADDR13") (class "Default")
      (node (ref "IC4") (pin "15") (pinfunction "6Q_15") (pintype "tri_state"))
      (node (ref "X1") (pin "A17") (pinfunction "B_A17") (pintype "passive"))
    )
    (net (code "49") (name "ADDR14") (class "Default")
      (node (ref "IC4") (pin "16") (pinfunction "7Q_16") (pintype "tri_state"))
      (node (ref "X1") (pin "A18") (pinfunction "B_A18") (pintype "passive"))
    )
    (net (code "50") (name "ADDR15") (class "Default")
      (node (ref "IC4") (pin "19") (pinfunction "8Q_19") (pintype "tri_state"))
      (node (ref "X1") (pin "A19") (pinfunction "B_A19") (pintype "passive"))
    )
    (net (code "51") (name "BRD-ADDR-REG0") (class "Default")
      (node (ref "IC2") (pin "14") (pinfunction "A_14") (pintype "input"))
      (node (ref "IC2") (pin "2") (pinfunction "A_2") (pintype "input"))
      (node (ref "X1") (pin "B6") (pinfunction "B_B6") (pintype "passive"))
    )
    (net (code "52") (name "BRD-ADDR-REG1") (class "Default")
      (node (ref "IC2") (pin "13") (pinfunction "B_13") (pintype "input"))
      (node (ref "IC2") (pin "3") (pinfunction "B_3") (pintype "input"))
      (node (ref "X1") (pin "B5") (pinfunction "B_B5") (pintype "passive"))
    )
    (net (code "53") (name "BRD-IN-ID0") (class "Default")
      (node (ref "IC12") (pin "14") (pinfunction "A_14") (pintype "input"))
      (node (ref "X1") (pin "B18") (pinfunction "B_B18") (pintype "passive"))
    )
    (net (code "54") (name "BRD-IN-ID1") (class "Default")
      (node (ref "IC12") (pin "13") (pinfunction "B_13") (pintype "input"))
      (node (ref "X1") (pin "B19") (pinfunction "B_B19") (pintype "passive"))
    )
    (net (code "55") (name "BRD-OUT-ID0") (class "Default")
      (node (ref "IC11") (pin "14") (pinfunction "A_14") (pintype "input"))
      (node (ref "X1") (pin "B14") (pinfunction "B_B14") (pintype "passive"))
    )
    (net (code "56") (name "BRD-OUT-ID1") (class "Default")
      (node (ref "IC11") (pin "13") (pinfunction "B_13") (pintype "input"))
      (node (ref "X1") (pin "B15") (pinfunction "B_B15") (pintype "passive"))
    )
    (net (code "57") (name "CLK0H") (class "Default")
      (node (ref "IC14") (pin "4") (pinfunction "O_4") (pintype "output"))
      (node (ref "IC16") (pin "11") (pinfunction "CLK_11") (pintype "input"))
      (node (ref "JP5") (pin "23") (pinfunction "23_23") (pintype "passive"))
    )
    (net (code "58") (name "CLK0L") (class "Default")
      (node (ref "IC14") (pin "1") (pinfunction "O_1") (pintype "output"))
      (node (ref "IC15") (pin "11") (pinfunction "CLK_11") (pintype "input"))
      (node (ref "JP5") (pin "25") (pinfunction "25_25") (pintype "passive"))
    )
    (net (code "59") (name "CLK1H") (class "Default")
      (node (ref "IC14") (pin "13") (pinfunction "O_13") (pintype "output"))
      (node (ref "IC18") (pin "11") (pinfunction "CLK_11") (pintype "input"))
      (node (ref "JP5") (pin "19") (pinfunction "19_19") (pintype "passive"))
    )
    (net (code "60") (name "CLK1L") (class "Default")
      (node (ref "IC14") (pin "10") (pinfunction "O_10") (pintype "output"))
      (node (ref "IC17") (pin "11") (pinfunction "CLK_11") (pintype "input"))
      (node (ref "JP5") (pin "21") (pinfunction "21_21") (pintype "passive"))
    )
    (net (code "61") (name "CLK2H") (class "Default")
      (node (ref "IC20") (pin "4") (pinfunction "O_4") (pintype "output"))
      (node (ref "IC22") (pin "11") (pinfunction "CLK_11") (pintype "input"))
      (node (ref "JP5") (pin "24") (pinfunction "24_24") (pintype "passive"))
    )
    (net (code "62") (name "CLK2L") (class "Default")
      (node (ref "IC20") (pin "1") (pinfunction "O_1") (pintype "output"))
      (node (ref "IC21") (pin "11") (pinfunction "CLK_11") (pintype "input"))
      (node (ref "JP5") (pin "26") (pinfunction "26_26") (pintype "passive"))
    )
    (net (code "63") (name "CLK3H") (class "Default")
      (node (ref "IC20") (pin "13") (pinfunction "O_13") (pintype "output"))
      (node (ref "IC24") (pin "11") (pinfunction "CLK_11") (pintype "input"))
      (node (ref "JP5") (pin "20") (pinfunction "20_20") (pintype "passive"))
    )
    (net (code "64") (name "CLK3L") (class "Default")
      (node (ref "IC20") (pin "10") (pinfunction "O_10") (pintype "output"))
      (node (ref "IC23") (pin "11") (pinfunction "CLK_11") (pintype "input"))
      (node (ref "JP5") (pin "22") (pinfunction "22_22") (pintype "passive"))
    )
    (net (code "65") (name "DATA-REG-IN-ID0") (class "Default")
      (node (ref "IC12") (pin "2") (pinfunction "A_2") (pintype "input"))
      (node (ref "X1") (pin "B16") (pinfunction "B_B16") (pintype "passive"))
    )
    (net (code "66") (name "DATA-REG-IN-ID1") (class "Default")
      (node (ref "IC12") (pin "3") (pinfunction "B_3") (pintype "input"))
      (node (ref "X1") (pin "B17") (pinfunction "B_B17") (pintype "passive"))
    )
    (net (code "67") (name "DATA-REG-OUT-ID0") (class "Default")
      (node (ref "IC11") (pin "2") (pinfunction "A_2") (pintype "input"))
      (node (ref "X1") (pin "B12") (pinfunction "B_B12") (pintype "passive"))
    )
    (net (code "68") (name "DATA-REG-OUT-ID1") (class "Default")
      (node (ref "IC11") (pin "3") (pinfunction "B_3") (pintype "input"))
      (node (ref "X1") (pin "B13") (pinfunction "B_B13") (pintype "passive"))
    )
    (net (code "69") (name "DATA-REG-RD-HI") (class "Default")
      (node (ref "IC1") (pin "5") (pinfunction "I_5") (pintype "input"))
      (node (ref "X1") (pin "B22") (pinfunction "B_B22") (pintype "passive"))
    )
    (net (code "70") (name "DATA-REG-RD-LO") (class "Default")
      (node (ref "IC1") (pin "1") (pinfunction "I_1") (pintype "input"))
      (node (ref "X1") (pin "B20") (pinfunction "B_B20") (pintype "passive"))
    )
    (net (code "71") (name "DATA-REG-WR-HI") (class "Default")
      (node (ref "IC1") (pin "9") (pinfunction "I_9") (pintype "input"))
      (node (ref "X1") (pin "B23") (pinfunction "B_B23") (pintype "passive"))
    )
    (net (code "72") (name "DATA-REG-WR-LO") (class "Default")
      (node (ref "IC1") (pin "3") (pinfunction "I_3") (pintype "input"))
      (node (ref "X1") (pin "B21") (pinfunction "B_B21") (pintype "passive"))
    )
    (net (code "73") (name "DATA0") (class "Default")
      (node (ref "IC7") (pin "2") (pinfunction "A1_2") (pintype "bidirectional"))
      (node (ref "IC9") (pin "2") (pinfunction "A1_2") (pintype "bidirectional"))
      (node (ref "X1") (pin "A20") (pinfunction "B_A20") (pintype "passive"))
    )
    (net (code "74") (name "DATA1") (class "Default")
      (node (ref "IC7") (pin "3") (pinfunction "A2_3") (pintype "bidirectional"))
      (node (ref "IC9") (pin "3") (pinfunction "A2_3") (pintype "bidirectional"))
      (node (ref "X1") (pin "A21") (pinfunction "B_A21") (pintype "passive"))
    )
    (net (code "75") (name "DATA2") (class "Default")
      (node (ref "IC7") (pin "4") (pinfunction "A3_4") (pintype "bidirectional"))
      (node (ref "IC9") (pin "4") (pinfunction "A3_4") (pintype "bidirectional"))
      (node (ref "X1") (pin "A22") (pinfunction "B_A22") (pintype "passive"))
    )
    (net (code "76") (name "DATA3") (class "Default")
      (node (ref "IC7") (pin "5") (pinfunction "A4_5") (pintype "bidirectional"))
      (node (ref "IC9") (pin "5") (pinfunction "A4_5") (pintype "bidirectional"))
      (node (ref "X1") (pin "A23") (pinfunction "B_A23") (pintype "passive"))
    )
    (net (code "77") (name "DATA4") (class "Default")
      (node (ref "IC7") (pin "6") (pinfunction "A5_6") (pintype "bidirectional"))
      (node (ref "IC9") (pin "6") (pinfunction "A5_6") (pintype "bidirectional"))
      (node (ref "X1") (pin "A24") (pinfunction "B_A24") (pintype "passive"))
    )
    (net (code "78") (name "DATA5") (class "Default")
      (node (ref "IC7") (pin "7") (pinfunction "A6_7") (pintype "bidirectional"))
      (node (ref "IC9") (pin "7") (pinfunction "A6_7") (pintype "bidirectional"))
      (node (ref "X1") (pin "A25") (pinfunction "B_A25") (pintype "passive"))
    )
    (net (code "79") (name "DATA6") (class "Default")
      (node (ref "IC7") (pin "8") (pinfunction "A7_8") (pintype "bidirectional"))
      (node (ref "IC9") (pin "8") (pinfunction "A7_8") (pintype "bidirectional"))
      (node (ref "X1") (pin "A26") (pinfunction "B_A26") (pintype "passive"))
    )
    (net (code "80") (name "DATA7") (class "Default")
      (node (ref "IC7") (pin "9") (pinfunction "A8_9") (pintype "bidirectional"))
      (node (ref "IC9") (pin "9") (pinfunction "A8_9") (pintype "bidirectional"))
      (node (ref "X1") (pin "A27") (pinfunction "B_A27") (pintype "passive"))
    )
    (net (code "81") (name "DATA8") (class "Default")
      (node (ref "IC8") (pin "2") (pinfunction "A1_2") (pintype "bidirectional"))
      (node (ref "X1") (pin "C23") (pinfunction "B_C23") (pintype "passive"))
    )
    (net (code "82") (name "DATA9") (class "Default")
      (node (ref "IC8") (pin "3") (pinfunction "A2_3") (pintype "bidirectional"))
      (node (ref "X1") (pin "C24") (pinfunction "B_C24") (pintype "passive"))
    )
    (net (code "83") (name "DATA10") (class "Default")
      (node (ref "IC8") (pin "4") (pinfunction "A3_4") (pintype "bidirectional"))
      (node (ref "X1") (pin "C25") (pinfunction "B_C25") (pintype "passive"))
    )
    (net (code "84") (name "DATA11") (class "Default")
      (node (ref "IC8") (pin "5") (pinfunction "A4_5") (pintype "bidirectional"))
      (node (ref "X1") (pin "C26") (pinfunction "B_C26") (pintype "passive"))
    )
    (net (code "85") (name "DATA12") (class "Default")
      (node (ref "IC8") (pin "6") (pinfunction "A5_6") (pintype "bidirectional"))
      (node (ref "X1") (pin "C27") (pinfunction "B_C27") (pintype "passive"))
    )
    (net (code "86") (name "DATA13") (class "Default")
      (node (ref "IC8") (pin "7") (pinfunction "A6_7") (pintype "bidirectional"))
      (node (ref "X1") (pin "C28") (pinfunction "B_C28") (pintype "passive"))
    )
    (net (code "87") (name "DATA14") (class "Default")
      (node (ref "IC8") (pin "8") (pinfunction "A7_8") (pintype "bidirectional"))
      (node (ref "X1") (pin "C29") (pinfunction "B_C29") (pintype "passive"))
    )
    (net (code "88") (name "DATA15") (class "Default")
      (node (ref "IC8") (pin "9") (pinfunction "A8_9") (pintype "bidirectional"))
      (node (ref "X1") (pin "C30") (pinfunction "B_C30") (pintype "passive"))
    )
    (net (code "89") (name "DIR") (class "Default")
      (node (ref "IC6") (pin "8") (pinfunction "O_8") (pintype "output"))
      (node (ref "IC7") (pin "1") (pinfunction "DIR_1") (pintype "input"))
      (node (ref "IC8") (pin "1") (pinfunction "DIR_1") (pintype "input"))
      (node (ref "IC9") (pin "1") (pinfunction "DIR_1") (pintype "input"))
    )
    (net (code "90") (name "GND") (class "Default")
      (node (ref "C1") (pin "2") (pinfunction "2_2") (pintype "passive"))
      (node (ref "C10") (pin "2") (pinfunction "2_2") (pintype "passive"))
      (node (ref "C11") (pin "2") (pinfunction "2_2") (pintype "passive"))
      (node (ref "C12") (pin "2") (pinfunction "2_2") (pintype "passive"))
      (node (ref "C13") (pin "2") (pinfunction "2_2") (pintype "passive"))
      (node (ref "C14") (pin "2") (pinfunction "2_2") (pintype "passive"))
      (node (ref "C15") (pin "2") (pinfunction "2_2") (pintype "passive"))
      (node (ref "C16") (pin "2") (pinfunction "2_2") (pintype "passive"))
      (node (ref "C17") (pin "2") (pinfunction "2_2") (pintype "passive"))
      (node (ref "C18") (pin "2") (pinfunction "2_2") (pintype "passive"))
      (node (ref "C19") (pin "2") (pinfunction "2_2") (pintype "passive"))
      (node (ref "C2") (pin "2") (pinfunction "2_2") (pintype "passive"))
      (node (ref "C20") (pin "2") (pinfunction "2_2") (pintype "passive"))
      (node (ref "C21") (pin "2") (pinfunction "2_2") (pintype "passive"))
      (node (ref "C22") (pin "2") (pinfunction "2_2") (pintype "passive"))
      (node (ref "C23") (pin "2") (pinfunction "2_2") (pintype "passive"))
      (node (ref "C24") (pin "2") (pinfunction "2_2") (pintype "passive"))
      (node (ref "C3") (pin "2") (pinfunction "2_2") (pintype "passive"))
      (node (ref "C4") (pin "2") (pinfunction "2_2") (pintype "passive"))
      (node (ref "C5") (pin "2") (pinfunction "2_2") (pintype "passive"))
      (node (ref "C6") (pin "2") (pinfunction "2_2") (pintype "passive"))
      (node (ref "C7") (pin "2") (pinfunction "2_2") (pintype "passive"))
      (node (ref "C8") (pin "2") (pinfunction "2_2") (pintype "passive"))
      (node (ref "C9") (pin "2") (pinfunction "2_2") (pintype "passive"))
      (node (ref "IC10") (pin "10") (pinfunction "GND_10") (pintype "power_in"))
      (node (ref "JP5") (pin "1") (pinfunction "1_1") (pintype "passive"))
      (node (ref "JP5") (pin "2") (pinfunction "2_2") (pintype "passive"))
      (node (ref "JP5") (pin "27") (pinfunction "27_27") (pintype "passive"))
      (node (ref "JP5") (pin "28") (pinfunction "28_28") (pintype "passive"))
      (node (ref "X1") (pin "A1") (pinfunction "B_A1") (pintype "passive"))
      (node (ref "X1") (pin "A32") (pinfunction "B_A32") (pintype "passive"))
      (node (ref "X1") (pin "B1") (pinfunction "B_B1") (pintype "passive"))
      (node (ref "X1") (pin "B32") (pinfunction "B_B32") (pintype "passive"))
      (node (ref "X1") (pin "C1") (pinfunction "B_C1") (pintype "passive"))
      (node (ref "X1") (pin "C32") (pinfunction "B_C32") (pintype "passive"))
    )
    (net (code "91") (name "H{slash}L-SWAP") (class "Default")
      (node (ref "IC5") (pin "13") (pinfunction "I1_13") (pintype "input"))
      (node (ref "IC6") (pin "1") (pinfunction "I0_1") (pintype "input"))
      (node (ref "IC6") (pin "2") (pinfunction "I1_2") (pintype "input"))
      (node (ref "X1") (pin "A30") (pinfunction "B_A30") (pintype "passive"))
    )
    (net (code "92") (name "Net-(IC1E-O)") (class "Default")
      (node (ref "IC1") (pin "10") (pinfunction "O_10") (pintype "output"))
      (node (ref "IC2") (pin "1") (pinfunction "G_1") (pintype "input"))
    )
    (net (code "93") (name "Net-(IC1F-I)") (class "Default")
      (node (ref "IC1") (pin "13") (pinfunction "I_13") (pintype "input"))
      (node (ref "JP1") (pin "2") (pinfunction "2_2") (pintype "passive"))
      (node (ref "JP1") (pin "4") (pinfunction "4_4") (pintype "passive"))
      (node (ref "JP1") (pin "6") (pinfunction "6_6") (pintype "passive"))
      (node (ref "JP1") (pin "8") (pinfunction "8_8") (pintype "passive"))
    )
    (net (code "94") (name "Net-(IC1F-O)") (class "Default")
      (node (ref "IC1") (pin "12") (pinfunction "O_12") (pintype "output"))
      (node (ref "IC3") (pin "11") (pinfunction "CLK_11") (pintype "input"))
      (node (ref "IC4") (pin "11") (pinfunction "CLK_11") (pintype "input"))
    )
    (net (code "95") (name "Net-(IC2A-Y0)") (class "Default")
      (node (ref "IC2") (pin "4") (pinfunction "Y0_4") (pintype "output"))
      (node (ref "JP1") (pin "1") (pinfunction "1_1") (pintype "passive"))
    )
    (net (code "96") (name "Net-(IC2A-Y1)") (class "Default")
      (node (ref "IC2") (pin "5") (pinfunction "Y1_5") (pintype "output"))
      (node (ref "JP1") (pin "3") (pinfunction "3_3") (pintype "passive"))
    )
    (net (code "97") (name "Net-(IC2A-Y2)") (class "Default")
      (node (ref "IC2") (pin "6") (pinfunction "Y2_6") (pintype "output"))
      (node (ref "JP1") (pin "5") (pinfunction "5_5") (pintype "passive"))
    )
    (net (code "98") (name "Net-(IC2A-Y3)") (class "Default")
      (node (ref "IC2") (pin "7") (pinfunction "Y3_7") (pintype "output"))
      (node (ref "JP1") (pin "7") (pinfunction "7_7") (pintype "passive"))
    )
    (net (code "99") (name "Net-(IC2B-G)") (class "Default")
      (node (ref "IC2") (pin "15") (pinfunction "G_15") (pintype "input"))
      (node (ref "IC6") (pin "6") (pinfunction "O_6") (pintype "output"))
    )
    (net (code "100") (name "Net-(IC2B-Y0)") (class "Default")
      (node (ref "IC2") (pin "12") (pinfunction "Y0_12") (pintype "output"))
      (node (ref "JP2") (pin "1") (pinfunction "1_1") (pintype "passive"))
    )
    (net (code "101") (name "Net-(IC2B-Y1)") (class "Default")
      (node (ref "IC2") (pin "11") (pinfunction "Y1_11") (pintype "output"))
      (node (ref "JP2") (pin "3") (pinfunction "3_3") (pintype "passive"))
    )
    (net (code "102") (name "Net-(IC2B-Y2)") (class "Default")
      (node (ref "IC2") (pin "10") (pinfunction "Y2_10") (pintype "output"))
      (node (ref "JP2") (pin "5") (pinfunction "5_5") (pintype "passive"))
    )
    (net (code "103") (name "Net-(IC2B-Y3)") (class "Default")
      (node (ref "IC2") (pin "9") (pinfunction "Y3_9") (pintype "output"))
      (node (ref "JP2") (pin "7") (pinfunction "7_7") (pintype "passive"))
    )
    (net (code "104") (name "Net-(IC3A-OC)") (class "Default")
      (node (ref "IC3") (pin "1") (pinfunction "OC_1") (pintype "input"))
      (node (ref "IC4") (pin "1") (pinfunction "OC_1") (pintype "input"))
      (node (ref "JP2") (pin "2") (pinfunction "2_2") (pintype "passive"))
      (node (ref "JP2") (pin "4") (pinfunction "4_4") (pintype "passive"))
      (node (ref "JP2") (pin "6") (pinfunction "6_6") (pintype "passive"))
      (node (ref "JP2") (pin "8") (pinfunction "8_8") (pintype "passive"))
    )
    (net (code "105") (name "Net-(IC5A-O)") (class "Default")
      (node (ref "IC5") (pin "10") (pinfunction "I1_10") (pintype "input"))
      (node (ref "IC5") (pin "12") (pinfunction "I0_12") (pintype "input"))
      (node (ref "IC5") (pin "3") (pinfunction "O_3") (pintype "output"))
      (node (ref "IC5") (pin "4") (pinfunction "I0_4") (pintype "input"))
      (node (ref "IC5") (pin "5") (pinfunction "I1_5") (pintype "input"))
    )
    (net (code "106") (name "Net-(IC5B-O)") (class "Default")
      (node (ref "IC5") (pin "6") (pinfunction "O_6") (pintype "output"))
      (node (ref "IC8") (pin "19") (pinfunction "G_19") (pintype "input"))
    )
    (net (code "107") (name "Net-(IC5C-I0)") (class "Default")
      (node (ref "IC5") (pin "9") (pinfunction "I0_9") (pintype "input"))
      (node (ref "IC6") (pin "3") (pinfunction "O_3") (pintype "output"))
    )
    (net (code "108") (name "Net-(IC5C-O)") (class "Default")
      (node (ref "IC5") (pin "8") (pinfunction "O_8") (pintype "output"))
      (node (ref "IC7") (pin "19") (pinfunction "G_19") (pintype "input"))
    )
    (net (code "109") (name "Net-(IC5D-O)") (class "Default")
      (node (ref "IC5") (pin "11") (pinfunction "O_11") (pintype "output"))
      (node (ref "IC9") (pin "19") (pinfunction "G_19") (pintype "input"))
    )
    (net (code "110") (name "Net-(IC11B-Y0)") (class "Default")
      (node (ref "IC11") (pin "12") (pinfunction "Y0_12") (pintype "output"))
      (node (ref "JP3") (pin "1") (pinfunction "1_1") (pintype "passive"))
    )
    (net (code "111") (name "Net-(IC11B-Y1)") (class "Default")
      (node (ref "IC11") (pin "11") (pinfunction "Y1_11") (pintype "output"))
      (node (ref "JP3") (pin "3") (pinfunction "3_3") (pintype "passive"))
    )
    (net (code "112") (name "Net-(IC11B-Y2)") (class "Default")
      (node (ref "IC11") (pin "10") (pinfunction "Y2_10") (pintype "output"))
      (node (ref "JP3") (pin "5") (pinfunction "5_5") (pintype "passive"))
    )
    (net (code "113") (name "Net-(IC11B-Y3)") (class "Default")
      (node (ref "IC11") (pin "9") (pinfunction "Y3_9") (pintype "output"))
      (node (ref "JP3") (pin "7") (pinfunction "7_7") (pintype "passive"))
    )
    (net (code "114") (name "Net-(IC12B-Y0)") (class "Default")
      (node (ref "IC12") (pin "12") (pinfunction "Y0_12") (pintype "output"))
      (node (ref "JP4") (pin "1") (pinfunction "1_1") (pintype "passive"))
    )
    (net (code "115") (name "Net-(IC12B-Y1)") (class "Default")
      (node (ref "IC12") (pin "11") (pinfunction "Y1_11") (pintype "output"))
      (node (ref "JP4") (pin "3") (pinfunction "3_3") (pintype "passive"))
    )
    (net (code "116") (name "Net-(IC12B-Y2)") (class "Default")
      (node (ref "IC12") (pin "10") (pinfunction "Y2_10") (pintype "output"))
      (node (ref "JP4") (pin "5") (pinfunction "5_5") (pintype "passive"))
    )
    (net (code "117") (name "Net-(IC12B-Y3)") (class "Default")
      (node (ref "IC12") (pin "9") (pinfunction "Y3_9") (pintype "output"))
      (node (ref "JP4") (pin "7") (pinfunction "7_7") (pintype "passive"))
    )
    (net (code "118") (name "Net-(IC13A-O)") (class "Default")
      (node (ref "IC13") (pin "3") (pinfunction "O_3") (pintype "output"))
      (node (ref "IC15") (pin "1") (pinfunction "OC_1") (pintype "input"))
    )
    (net (code "119") (name "Net-(IC13B-O)") (class "Default")
      (node (ref "IC13") (pin "6") (pinfunction "O_6") (pintype "output"))
      (node (ref "IC16") (pin "1") (pinfunction "OC_1") (pintype "input"))
    )
    (net (code "120") (name "Net-(IC13C-O)") (class "Default")
      (node (ref "IC13") (pin "8") (pinfunction "O_8") (pintype "output"))
      (node (ref "IC17") (pin "1") (pinfunction "OC_1") (pintype "input"))
    )
    (net (code "121") (name "Net-(IC13D-O)") (class "Default")
      (node (ref "IC13") (pin "11") (pinfunction "O_11") (pintype "output"))
      (node (ref "IC18") (pin "1") (pinfunction "OC_1") (pintype "input"))
    )
    (net (code "122") (name "Net-(IC19A-O)") (class "Default")
      (node (ref "IC19") (pin "3") (pinfunction "O_3") (pintype "output"))
      (node (ref "IC21") (pin "1") (pinfunction "OC_1") (pintype "input"))
    )
    (net (code "123") (name "Net-(IC19B-O)") (class "Default")
      (node (ref "IC19") (pin "6") (pinfunction "O_6") (pintype "output"))
      (node (ref "IC22") (pin "1") (pinfunction "OC_1") (pintype "input"))
    )
    (net (code "124") (name "Net-(IC19C-O)") (class "Default")
      (node (ref "IC19") (pin "8") (pinfunction "O_8") (pintype "output"))
      (node (ref "IC23") (pin "1") (pinfunction "OC_1") (pintype "input"))
    )
    (net (code "125") (name "Net-(IC19D-O)") (class "Default")
      (node (ref "IC19") (pin "11") (pinfunction "O_11") (pintype "output"))
      (node (ref "IC24") (pin "1") (pinfunction "OC_1") (pintype "input"))
    )
    (net (code "126") (name "REG-FUNC") (class "Default")
      (node (ref "IC6") (pin "12") (pinfunction "I0_12") (pintype "input"))
      (node (ref "IC6") (pin "13") (pinfunction "I1_13") (pintype "input"))
      (node (ref "X1") (pin "B7") (pinfunction "B_B7") (pintype "passive"))
    )
    (net (code "127") (name "VCC") (class "Default")
      (node (ref "C1") (pin "1") (pinfunction "1_1") (pintype "passive"))
      (node (ref "C10") (pin "1") (pinfunction "1_1") (pintype "passive"))
      (node (ref "C11") (pin "1") (pinfunction "1_1") (pintype "passive"))
      (node (ref "C12") (pin "1") (pinfunction "1_1") (pintype "passive"))
      (node (ref "C13") (pin "1") (pinfunction "1_1") (pintype "passive"))
      (node (ref "C14") (pin "1") (pinfunction "1_1") (pintype "passive"))
      (node (ref "C15") (pin "1") (pinfunction "1_1") (pintype "passive"))
      (node (ref "C16") (pin "1") (pinfunction "1_1") (pintype "passive"))
      (node (ref "C17") (pin "1") (pinfunction "1_1") (pintype "passive"))
      (node (ref "C18") (pin "1") (pinfunction "1_1") (pintype "passive"))
      (node (ref "C19") (pin "1") (pinfunction "1_1") (pintype "passive"))
      (node (ref "C2") (pin "1") (pinfunction "1_1") (pintype "passive"))
      (node (ref "C20") (pin "1") (pinfunction "1_1") (pintype "passive"))
      (node (ref "C21") (pin "1") (pinfunction "1_1") (pintype "passive"))
      (node (ref "C22") (pin "1") (pinfunction "1_1") (pintype "passive"))
      (node (ref "C23") (pin "1") (pinfunction "1_1") (pintype "passive"))
      (node (ref "C24") (pin "1") (pinfunction "1_1") (pintype "passive"))
      (node (ref "C3") (pin "1") (pinfunction "1_1") (pintype "passive"))
      (node (ref "C4") (pin "1") (pinfunction "1_1") (pintype "passive"))
      (node (ref "C5") (pin "1") (pinfunction "1_1") (pintype "passive"))
      (node (ref "C6") (pin "1") (pinfunction "1_1") (pintype "passive"))
      (node (ref "C7") (pin "1") (pinfunction "1_1") (pintype "passive"))
      (node (ref "C8") (pin "1") (pinfunction "1_1") (pintype "passive"))
      (node (ref "C9") (pin "1") (pinfunction "1_1") (pintype "passive"))
      (node (ref "IC10") (pin "20") (pinfunction "VCC_20") (pintype "power_in"))
      (node (ref "RN1") (pin "1") (pinfunction "1_1") (pintype "passive"))
      (node (ref "RN2") (pin "1") (pinfunction "1_1") (pintype "passive"))
      (node (ref "X1") (pin "A2") (pinfunction "B_A2") (pintype "passive"))
      (node (ref "X1") (pin "A31") (pinfunction "B_A31") (pintype "passive"))
      (node (ref "X1") (pin "B2") (pinfunction "B_B2") (pintype "passive"))
      (node (ref "X1") (pin "B31") (pinfunction "B_B31") (pintype "passive"))
      (node (ref "X1") (pin "C2") (pinfunction "B_C2") (pintype "passive"))
      (node (ref "X1") (pin "C31") (pinfunction "B_C31") (pintype "passive"))
    )
    (net (code "128") (name "unconnected-(X1AH-B-PadB10)") (class "Default")
      (node (ref "X1") (pin "B10") (pinfunction "B_B10") (pintype "passive"))
    )
    (net (code "129") (name "unconnected-(X1AI-B-PadB11)") (class "Default")
      (node (ref "X1") (pin "B11") (pinfunction "B_B11") (pintype "passive"))
    )
    (net (code "130") (name "unconnected-(X1AW-B-PadB24)") (class "Default")
      (node (ref "X1") (pin "B24") (pinfunction "B_B24") (pintype "passive"))
    )
    (net (code "131") (name "unconnected-(X1AX-B-PadB25)") (class "Default")
      (node (ref "X1") (pin "B25") (pinfunction "B_B25") (pintype "passive"))
    )
    (net (code "132") (name "unconnected-(X1AY-B-PadB26)") (class "Default")
      (node (ref "X1") (pin "B26") (pinfunction "B_B26") (pintype "passive"))
    )
    (net (code "133") (name "unconnected-(X1AZ-B-PadB27)") (class "Default")
      (node (ref "X1") (pin "B27") (pinfunction "B_B27") (pintype "passive"))
    )
    (net (code "134") (name "unconnected-(X1BA-B-PadB28)") (class "Default")
      (node (ref "X1") (pin "B28") (pinfunction "B_B28") (pintype "passive"))
    )
    (net (code "135") (name "unconnected-(X1BB-B-PadB29)") (class "Default")
      (node (ref "X1") (pin "B29") (pinfunction "B_B29") (pintype "passive"))
    )
    (net (code "136") (name "unconnected-(X1BD-B-PadB30)") (class "Default")
      (node (ref "X1") (pin "B30") (pinfunction "B_B30") (pintype "passive"))
    )
    (net (code "137") (name "unconnected-(X1BL-B-PadB9)") (class "Default")
      (node (ref "X1") (pin "B9") (pinfunction "B_B9") (pintype "passive"))
    )
    (net (code "138") (name "unconnected-(X1BN-B-PadC10)") (class "Default")
      (node (ref "X1") (pin "C10") (pinfunction "B_C10") (pintype "passive"))
    )
    (net (code "139") (name "unconnected-(X1BO-B-PadC11)") (class "Default")
      (node (ref "X1") (pin "C11") (pinfunction "B_C11") (pintype "passive"))
    )
    (net (code "140") (name "unconnected-(X1BP-B-PadC12)") (class "Default")
      (node (ref "X1") (pin "C12") (pinfunction "B_C12") (pintype "passive"))
    )
    (net (code "141") (name "unconnected-(X1BQ-B-PadC13)") (class "Default")
      (node (ref "X1") (pin "C13") (pinfunction "B_C13") (pintype "passive"))
    )
    (net (code "142") (name "unconnected-(X1BR-B-PadC14)") (class "Default")
      (node (ref "X1") (pin "C14") (pinfunction "B_C14") (pintype "passive"))
    )
    (net (code "143") (name "unconnected-(X1BS-B-PadC15)") (class "Default")
      (node (ref "X1") (pin "C15") (pinfunction "B_C15") (pintype "passive"))
    )
    (net (code "144") (name "unconnected-(X1BT-B-PadC16)") (class "Default")
      (node (ref "X1") (pin "C16") (pinfunction "B_C16") (pintype "passive"))
    )
    (net (code "145") (name "unconnected-(X1BU-B-PadC17)") (class "Default")
      (node (ref "X1") (pin "C17") (pinfunction "B_C17") (pintype "passive"))
    )
    (net (code "146") (name "unconnected-(X1BV-B-PadC18)") (class "Default")
      (node (ref "X1") (pin "C18") (pinfunction "B_C18") (pintype "passive"))
    )
    (net (code "147") (name "unconnected-(X1BW-B-PadC19)") (class "Default")
      (node (ref "X1") (pin "C19") (pinfunction "B_C19") (pintype "passive"))
    )
    (net (code "148") (name "unconnected-(X1BY-B-PadC20)") (class "Default")
      (node (ref "X1") (pin "C20") (pinfunction "B_C20") (pintype "passive"))
    )
    (net (code "149") (name "unconnected-(X1BZ-B-PadC21)") (class "Default")
      (node (ref "X1") (pin "C21") (pinfunction "B_C21") (pintype "passive"))
    )
    (net (code "150") (name "unconnected-(X1CA-B-PadC22)") (class "Default")
      (node (ref "X1") (pin "C22") (pinfunction "B_C22") (pintype "passive"))
    )
    (net (code "151") (name "unconnected-(X1CM-B-PadC4)") (class "Default")
      (node (ref "X1") (pin "C4") (pinfunction "B_C4") (pintype "passive"))
    )
    (net (code "152") (name "unconnected-(X1CN-B-PadC5)") (class "Default")
      (node (ref "X1") (pin "C5") (pinfunction "B_C5") (pintype "passive"))
    )
    (net (code "153") (name "unconnected-(X1CO-B-PadC6)") (class "Default")
      (node (ref "X1") (pin "C6") (pinfunction "B_C6") (pintype "passive"))
    )
    (net (code "154") (name "unconnected-(X1CP-B-PadC7)") (class "Default")
      (node (ref "X1") (pin "C7") (pinfunction "B_C7") (pintype "passive"))
    )
    (net (code "155") (name "unconnected-(X1CQ-B-PadC8)") (class "Default")
      (node (ref "X1") (pin "C8") (pinfunction "B_C8") (pintype "passive"))
    )
    (net (code "156") (name "unconnected-(X1CR-B-PadC9)") (class "Default")
      (node (ref "X1") (pin "C9") (pinfunction "B_C9") (pintype "passive"))
    )
    (net (code "157") (name "unconnected-(X1U-B-PadA28)") (class "Default")
      (node (ref "X1") (pin "A28") (pinfunction "B_A28") (pintype "passive"))
    )
    (net (code "158") (name "unconnected-(X1V-B-PadA29)") (class "Default")
      (node (ref "X1") (pin "A29") (pinfunction "B_A29") (pintype "passive"))
    )
  )
)
